# PG09__TEMP_BALANCER.net
KiCad netlist of a schematic drawn in Altium Designer
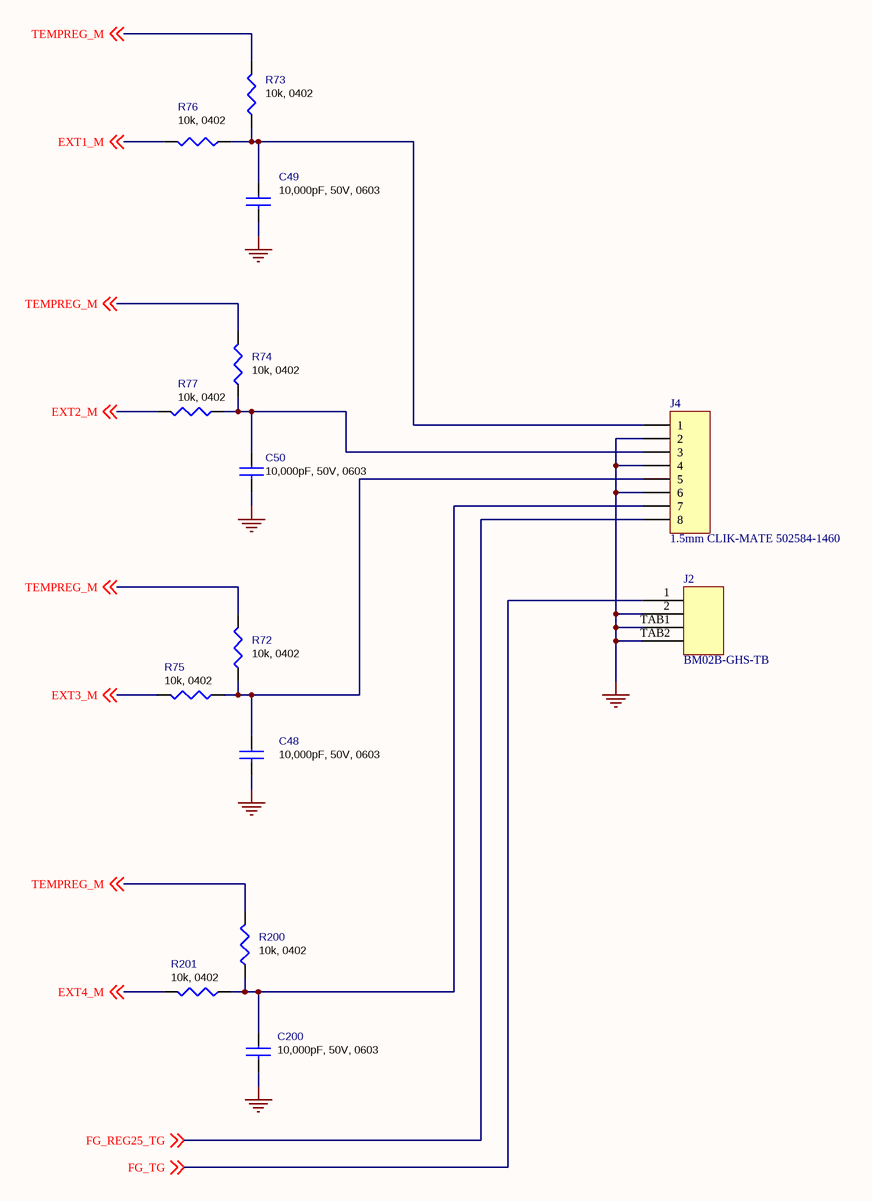
[diagram p0: PG09_ TEMP_BALANCER.SchDoc]

(export (version "E")
  (design (tool "Eeschema 10.0.6"))
  (components
    (comp (ref "C48")
      (value "10,000pF, 50V, 0603")
      (footprint "C0603")
      (description "CAP CER 10000PF 50V X7R 0603")
      (fields
        (field (name "MANUFACTURER") "TDK")
        (field (name "MANUFACTURER PART NUMBER") "CGA3E2X7R1H103K080AE")
      )
      (libsource (lib "*") (part "CAP-Generic-0603"))
    )
    (comp (ref "C49")
      (value "10,000pF, 50V, 0603")
      (footprint "C0603")
      (description "CAP CER 10000PF 50V X7R 0603")
      (fields
        (field (name "MANUFACTURER") "TDK")
        (field (name "MANUFACTURER PART NUMBER") "CGA3E2X7R1H103K080AE")
      )
      (libsource (lib "*") (part "CAP-Generic-0603"))
    )
    (comp (ref "C50")
      (value "10,000pF, 50V, 0603")
      (footprint "C0603")
      (description "CAP CER 10000PF 50V X7R 0603")
      (fields
        (field (name "MANUFACTURER") "TDK")
        (field (name "MANUFACTURER PART NUMBER") "CGA3E2X7R1H103K080AE")
      )
      (libsource (lib "*") (part "CAP-Generic-0603"))
    )
    (comp (ref "C200")
      (value "10,000pF, 50V, 0603")
      (footprint "C0603")
      (description "CAP CER 10000PF 50V X7R 0603")
      (fields
        (field (name "MANUFACTURER") "TDK")
        (field (name "MANUFACTURER PART NUMBER") "CGA3E2X7R1H103K080AE")
      )
      (libsource (lib "*") (part "CAP-Generic-0603"))
    )
    (comp (ref "J2")
      (value "BM02B-GHS-TB")
      (footprint "BM02B-GHS-TBT")
      (description "CONN HEADER GH TOP 2POS 1.25MM")
      (libsource (lib "Altium") (part "BM02B-GHS-TBT"))
    )
    (comp (ref "J4")
      (value "1.5mm CLIK-MATE 502584-1460")
      (footprint "CONN8_1P5MM_SM")
      (description "CONN RCPT 8POS 0.059 TIN SMD")
      (fields (field (name "MANUFACTURER") "Molex") (field (name "MANUFACTURER PART NUMBER") "502584-0860"))
      (libsource (lib "Miscellaneous Connectors") (part "Header 8"))
    )
    (comp (ref "R72")
      (value "10k, 0402")
      (footprint "R0402")
      (description "RES SMD 10K OHM 1% 1/16W 0402")
      (fields
        (field (name "MANUFACTURER") "Vishay Dale")
        (field (name "MANUFACTURER PART NUMBER") "CRCW040210K0FKTD")
      )
      (libsource (lib "Miscellaneous Devices") (part "R-Generic-0402"))
    )
    (comp (ref "R73")
      (value "10k, 0402")
      (footprint "R0402")
      (description "RES SMD 10K OHM 1% 1/16W 0402")
      (fields
        (field (name "MANUFACTURER") "Vishay Dale")
        (field (name "MANUFACTURER PART NUMBER") "CRCW040210K0FKTD")
      )
      (libsource (lib "Miscellaneous Devices") (part "R-Generic-0402"))
    )
    (comp (ref "R74")
      (value "10k, 0402")
      (footprint "R0402")
      (description "RES SMD 10K OHM 1% 1/16W 0402")
      (fields
        (field (name "MANUFACTURER") "Vishay Dale")
        (field (name "MANUFACTURER PART NUMBER") "CRCW040210K0FKTD")
      )
      (libsource (lib "Miscellaneous Devices") (part "R-Generic-0402"))
    )
    (comp (ref "R75")
      (value "10k, 0402")
      (footprint "R0402")
      (description "RES SMD 10K OHM 1% 1/16W 0402")
      (fields
        (field (name "MANUFACTURER") "Vishay Dale")
        (field (name "MANUFACTURER PART NUMBER") "CRCW040210K0FKTD")
      )
      (libsource (lib "Miscellaneous Devices") (part "R-Generic-0402"))
    )
    (comp (ref "R76")
      (value "10k, 0402")
      (footprint "R0402")
      (description "RES SMD 10K OHM 1% 1/16W 0402")
      (fields
        (field (name "MANUFACTURER") "Vishay Dale")
        (field (name "MANUFACTURER PART NUMBER") "CRCW040210K0FKTD")
      )
      (libsource (lib "Miscellaneous Devices") (part "R-Generic-0402"))
    )
    (comp (ref "R77")
      (value "10k, 0402")
      (footprint "R0402")
      (description "RES SMD 10K OHM 1% 1/16W 0402")
      (fields
        (field (name "MANUFACTURER") "Vishay Dale")
        (field (name "MANUFACTURER PART NUMBER") "CRCW040210K0FKTD")
      )
      (libsource (lib "Miscellaneous Devices") (part "R-Generic-0402"))
    )
    (comp (ref "R200")
      (value "10k, 0402")
      (footprint "R0402")
      (description "RES SMD 10K OHM 1% 1/16W 0402")
      (fields
        (field (name "MANUFACTURER") "Vishay Dale")
        (field (name "MANUFACTURER PART NUMBER") "CRCW040210K0FKTD")
      )
      (libsource (lib "Miscellaneous Devices") (part "R-Generic-0402"))
    )
    (comp (ref "R201")
      (value "10k, 0402")
      (footprint "R0402")
      (description "RES SMD 10K OHM 1% 1/16W 0402")
      (fields
        (field (name "MANUFACTURER") "Vishay Dale")
        (field (name "MANUFACTURER PART NUMBER") "CRCW040210K0FKTD")
      )
      (libsource (lib "Miscellaneous Devices") (part "R-Generic-0402"))
    )
  )
  (nets
    (net (code "1") (name "EXT1_M") (class "Default")
      (node (ref "R76") (pin "2") (pinfunction "2_2") (pintype "passive"))
    )
    (net (code "2") (name "EXT2_M") (class "Default")
      (node (ref "R77") (pin "2") (pinfunction "2_2") (pintype "passive"))
    )
    (net (code "3") (name "EXT3_M") (class "Default")
      (node (ref "R75") (pin "2") (pinfunction "2_2") (pintype "passive"))
    )
    (net (code "4") (name "EXT4_M") (class "Default")
      (node (ref "R201") (pin "2") (pinfunction "2_2") (pintype "passive"))
    )
    (net (code "5") (name "FG_REG25_TG") (class "Default")
      (node (ref "J4") (pin "8") (pinfunction "8_8") (pintype "passive"))
    )
    (net (code "6") (name "FG_TG") (class "Default")
      (node (ref "J2") (pin "1") (pinfunction "1_1") (pintype "passive"))
    )
    (net (code "7") (name "GND") (class "Default")
      (node (ref "C200") (pin "2") (pinfunction "2_2") (pintype "passive"))
      (node (ref "C48") (pin "2") (pinfunction "2_2") (pintype "passive"))
      (node (ref "C49") (pin "2") (pinfunction "2_2") (pintype "passive"))
      (node (ref "C50") (pin "2") (pinfunction "2_2") (pintype "passive"))
      (node (ref "J2") (pin "2") (pinfunction "2_2") (pintype "passive"))
      (node (ref "J2") (pin "TAB1") (pinfunction "TAB1_TAB1") (pintype "passive"))
      (node (ref "J2") (pin "TAB2") (pinfunction "TAB2_TAB2") (pintype "passive"))
      (node (ref "J4") (pin "2") (pinfunction "2_2") (pintype "passive"))
      (node (ref "J4") (pin "4") (pinfunction "4_4") (pintype "passive"))
      (node (ref "J4") (pin "6") (pinfunction "6_6") (pintype "passive"))
    )
    (net (code "8") (name "Net-(C48-Pad1)") (class "Default")
      (node (ref "C48") (pin "1") (pinfunction "1_1") (pintype "passive"))
      (node (ref "J4") (pin "5") (pinfunction "5_5") (pintype "passive"))
      (node (ref "R72") (pin "1") (pinfunction "1_1") (pintype "passive"))
      (node (ref "R75") (pin "1") (pinfunction "1_1") (pintype "passive"))
    )
    (net (code "9") (name "Net-(C49-Pad1)") (class "Default")
      (node (ref "C49") (pin "1") (pinfunction "1_1") (pintype "passive"))
      (node (ref "J4") (pin "1") (pinfunction "1_1") (pintype "passive"))
      (node (ref "R73") (pin "1") (pinfunction "1_1") (pintype "passive"))
      (node (ref "R76") (pin "1") (pinfunction "1_1") (pintype "passive"))
    )
    (net (code "10") (name "Net-(C50-Pad1)") (class "Default")
      (node (ref "C50") (pin "1") (pinfunction "1_1") (pintype "passive"))
      (node (ref "J4") (pin "3") (pinfunction "3_3") (pintype "passive"))
      (node (ref "R74") (pin "1") (pinfunction "1_1") (pintype "passive"))
      (node (ref "R77") (pin "1") (pinfunction "1_1") (pintype "passive"))
    )
    (net (code "11") (name "Net-(C200-Pad1)") (class "Default")
      (node (ref "C200") (pin "1") (pinfunction "1_1") (pintype "passive"))
      (node (ref "J4") (pin "7") (pinfunction "7_7") (pintype "passive"))
      (node (ref "R200") (pin "1") (pinfunction "1_1") (pintype "passive"))
      (node (ref "R201") (pin "1") (pinfunction "1_1") (pintype "passive"))
    )
    (net (code "12") (name "TEMPREG_M") (class "Default")
      (node (ref "R200") (pin "2") (pinfunction "2_2") (pintype "passive"))
      (node (ref "R72") (pin "2") (pinfunction "2_2") (pintype "passive"))
      (node (ref "R73") (pin "2") (pinfunction "2_2") (pintype "passive"))
      (node (ref "R74") (pin "2") (pinfunction "2_2") (pintype "passive"))
    )
  )
)
